# THlp.net
KiCad netlist of a schematic drawn in EAGLE
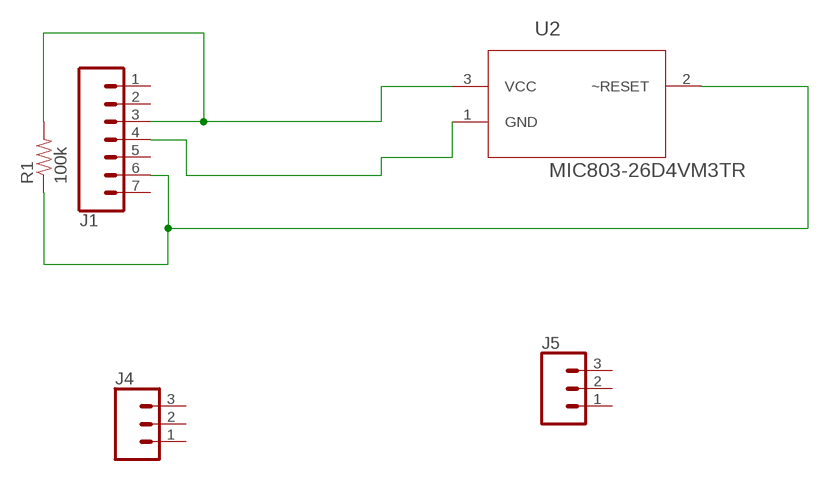
[diagram p0: schematic, sheet 1]

(export (version "E")
  (design (tool "Eeschema 10.0.6"))
  (components
    (comp (ref "J1")
      (value "CONN_07")
      (footprint "eagle-import:1X07")
      (libsource (lib "eagle-import") (part "CONN_07"))
    )
    (comp (ref "J4")
      (value "CONN_03PTH")
      (footprint "eagle-import:1X03")
      (libsource (lib "eagle-import") (part "CONN_03PTH"))
    )
    (comp (ref "J5")
      (value "CONN_03PTH")
      (footprint "eagle-import:1X03")
      (libsource (lib "eagle-import") (part "CONN_03PTH"))
    )
    (comp (ref "R1")
      (value "100k")
      (footprint "eagle-import:0603-RES")
      (libsource (lib "eagle-import") (part "RESISTOR0603-RES"))
    )
    (comp (ref "U2")
      (value "MIC803-26D4VM3TR")
      (footprint "eagle-import:SOT95P232X110-3N")
      (libsource (lib "eagle-import") (part "MIC803-26D4VM3TR"))
    )
  )
  (nets
    (net (code "1") (name "Net-(U2-GND)") (class "Default")
      (node (ref "J1") (pin "4") (pinfunction "4_4") (pintype "passive"))
      (node (ref "U2") (pin "1") (pinfunction "GND_1") (pintype "passive"))
    )
    (net (code "2") (name "Net-(U2-VCC)") (class "Default")
      (node (ref "J1") (pin "3") (pinfunction "3_3") (pintype "passive"))
      (node (ref "R1") (pin "2") (pinfunction "2_2") (pintype "passive"))
      (node (ref "U2") (pin "3") (pinfunction "VCC_3") (pintype "power_in"))
    )
    (net (code "3") (name "Net-(U2-~{RESET})") (class "Default")
      (node (ref "J1") (pin "6") (pinfunction "6_6") (pintype "passive"))
      (node (ref "R1") (pin "1") (pinfunction "1_1") (pintype "passive"))
      (node (ref "U2") (pin "2") (pinfunction "~{RESET}_2") (pintype "passive"))
    )
    (net (code "4") (name "unconnected-(J1-Pad1)") (class "Default")
      (node (ref "J1") (pin "1") (pinfunction "1_1") (pintype "passive"))
    )
    (net (code "5") (name "unconnected-(J1-Pad2)") (class "Default")
      (node (ref "J1") (pin "2") (pinfunction "2_2") (pintype "passive"))
    )
    (net (code "6") (name "unconnected-(J1-Pad5)") (class "Default")
      (node (ref "J1") (pin "5") (pinfunction "5_5") (pintype "passive"))
    )
    (net (code "7") (name "unconnected-(J1-Pad7)") (class "Default")
      (node (ref "J1") (pin "7") (pinfunction "7_7") (pintype "passive"))
    )
    (net (code "8") (name "unconnected-(J4-Pad1)") (class "Default")
      (node (ref "J4") (pin "1") (pinfunction "1_1") (pintype "passive"))
    )
    (net (code "9") (name "unconnected-(J4-Pad2)") (class "Default")
      (node (ref "J4") (pin "2") (pinfunction "2_2") (pintype "passive"))
    )
    (net (code "10") (name "unconnected-(J4-Pad3)") (class "Default")
      (node (ref "J4") (pin "3") (pinfunction "3_3") (pintype "passive"))
    )
    (net (code "11") (name "unconnected-(J5-Pad1)") (class "Default")
      (node (ref "J5") (pin "1") (pinfunction "1_1") (pintype "passive"))
    )
    (net (code "12") (name "unconnected-(J5-Pad2)") (class "Default")
      (node (ref "J5") (pin "2") (pinfunction "2_2") (pintype "passive"))
    )
    (net (code "13") (name "unconnected-(J5-Pad3)") (class "Default")
      (node (ref "J5") (pin "3") (pinfunction "3_3") (pintype "passive"))
    )
  )
)
